# 5_USB-C_Connector.net
KiCad netlist of a schematic drawn in Altium Designer
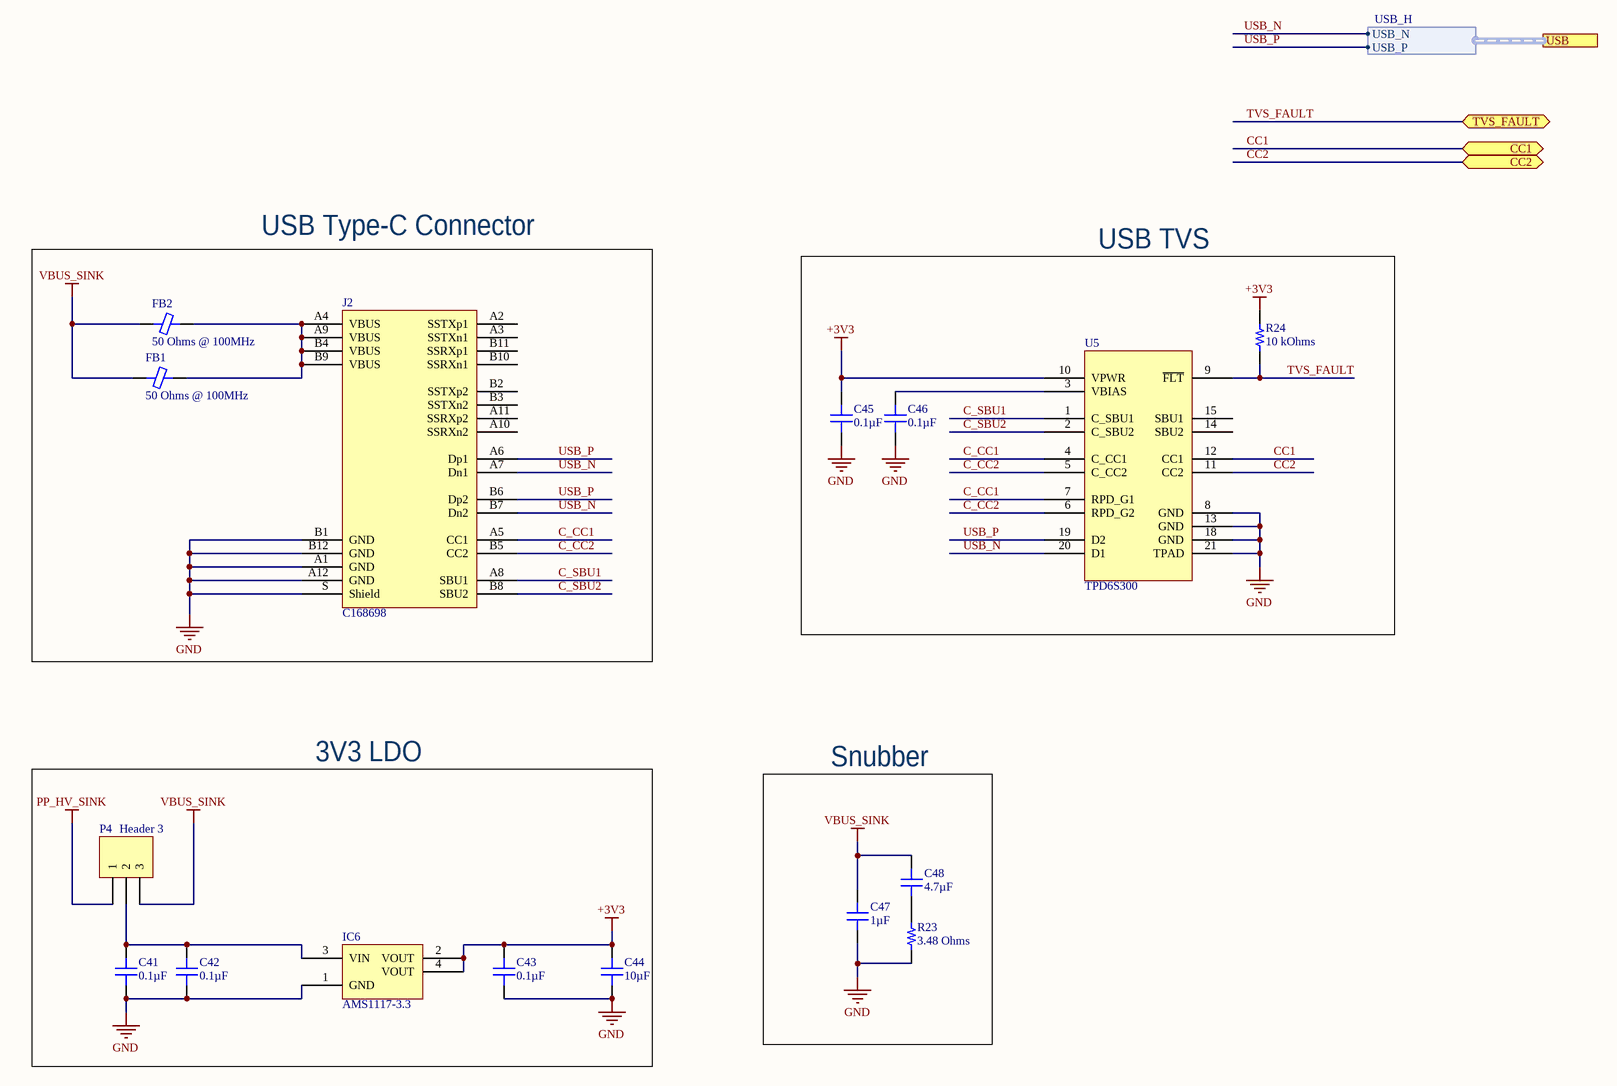
[diagram p0: [5] USB-C Connector.SchDoc]

(export (version "E")
  (design (tool "Eeschema 10.0.6"))
  (components
    (comp (ref "C41")
      (value "0.1µF")
      (footprint "CAP 0805_2012")
      (description "CAP CER 0.1UF 16V X7R 0805")
      (fields
        (field (name "PART NUMBER") "160R15W104KV4T")
        (field (name "MANUFACTURER") "Johanson Dielectrics Inc.")
      )
      (libsource (lib "Celestial Altium Library - altium_library") (part "Capacitor"))
    )
    (comp (ref "C42")
      (value "0.1µF")
      (footprint "CAP 0805_2012")
      (description "CAP CER 0.1UF 16V X7R 0805")
      (fields
        (field (name "PART NUMBER") "160R15W104KV4T")
        (field (name "MANUFACTURER") "Johanson Dielectrics Inc.")
      )
      (libsource (lib "Celestial Altium Library - altium_library") (part "Capacitor"))
    )
    (comp (ref "C43")
      (value "0.1µF")
      (footprint "CAP 0805_2012")
      (description "CAP CER 0.1UF 16V X7R 0805")
      (fields
        (field (name "PART NUMBER") "160R15W104KV4T")
        (field (name "MANUFACTURER") "Johanson Dielectrics Inc.")
      )
      (libsource (lib "Celestial Altium Library - altium_library") (part "Capacitor"))
    )
    (comp (ref "C44")
      (value "10µF")
      (footprint "CAP 1210_3225 - 2.8MM")
      (description "CAP CER 10UF 25V X7R 1210")
      (fields (field (name "PART NUMBER") "C1210C106K3RACAUTO") (field (name "MANUFACTURER") "KEMET"))
      (libsource (lib "Celestial Altium Library - altium_library") (part "Capacitor"))
    )
    (comp (ref "C45")
      (value "0.1µF")
      (footprint "CAP 0603_1608")
      (description "CAP CER 0.1UF 16V X7R 0603")
      (fields
        (field (name "PART NUMBER") "0603B104J160CT")
        (field (name "MANUFACTURER") "Walsin Technology Corporation")
      )
      (libsource (lib "Celestial Altium Library - altium_library") (part "Capacitor"))
    )
    (comp (ref "C46")
      (value "0.1µF")
      (footprint "CAP 0603_1608")
      (description "CAP CER 0.1UF 16V X7R 0603")
      (fields
        (field (name "PART NUMBER") "0603B104J160CT")
        (field (name "MANUFACTURER") "Walsin Technology Corporation")
      )
      (libsource (lib "Celestial Altium Library - altium_library") (part "Capacitor"))
    )
    (comp (ref "C47")
      (value "1µF")
      (footprint "CAP 0805_2012")
      (description "CAP CER 1UF 50V X7R 0805")
      (fields (field (name "PART NUMBER") "08055C105K4Z2A") (field (name "MANUFACTURER") "AVX Corporation"))
      (libsource (lib "Celestial Altium Library - altium_library") (part "Capacitor"))
    )
    (comp (ref "C48")
      (value "4.7µF")
      (footprint "CAP 0805_2012")
      (description "CAP CER 4.7UF 50V JB 0805")
      (fields
        (field (name "PART NUMBER") "C2012JB1H475K125AB")
        (field (name "MANUFACTURER") "TDK Corporation")
      )
      (libsource (lib "Celestial Altium Library - altium_library") (part "Capacitor"))
    )
    (comp (ref "FB1")
      (value "50 Ohms @ 100MHz")
      (footprint "FER 1206_3216")
      (description "FERRITE BEAD 50 OHM 1206 1LN")
      (fields
        (field (name "PART NUMBER") "BLM31SN500SZ1L")
        (field (name "MANUFACTURER") "Murata Electronics")
      )
      (libsource (lib "Celestial Altium Library - altium_library") (part "Ferrite Chip"))
    )
    (comp (ref "FB2")
      (value "50 Ohms @ 100MHz")
      (footprint "FER 1206_3216")
      (description "FERRITE BEAD 50 OHM 1206 1LN")
      (fields
        (field (name "PART NUMBER") "BLM31SN500SZ1L")
        (field (name "MANUFACTURER") "Murata Electronics")
      )
      (libsource (lib "Celestial Altium Library - altium_library") (part "Ferrite Chip"))
    )
    (comp (ref "IC6")
      (value "AMS1117-3.3")
      (footprint "ON SEMI SOT-223 ST(318H)")
      (description "IC REG LDO 3.3V 1A SOT223")
      (fields (field (name "PART NUMBER") "NCP1117ST33T3G") (field (name "MANUFACTURER") "ON Semiconductor"))
      (libsource (lib "Celestial Library Database") (part "ON Semi NCP1117"))
    )
    (comp (ref "J2")
      (value "C168698")
      (footprint "USB4055")
      (description "USB 3.1 TYPE C MID MOUNT HYBRID")
      (fields (field (name "MANUFACTURER") "Jing Extension"))
      (libsource (lib "Celestial Library Database") (part "USB 3.0 Type C"))
    )
    (comp (ref "P4")
      (value "Header 3")
      (footprint "3D FootPrint_Backup:HEADER 2.54MM - duplicate1")
      (description "Header, 3-Pin")
      (fields (field (name "PUBLISHER") "Altium Limited"))
      (libsource (lib "Miscellaneous Connectors") (part "Header 3"))
    )
    (comp (ref "R23")
      (value "3.48 Ohms")
      (footprint "RES 0805_2012")
      (description "RES SMD 3.48 OHM 1% 1/8W 0805")
      (fields (field (name "PART NUMBER") "RC0805FR-073R48L") (field (name "MANUFACTURER") "Yageo"))
      (libsource (lib "Celestial Altium Library - altium_library") (part "Resistor"))
    )
    (comp (ref "R24")
      (value "10 kOhms")
      (footprint "RES 0603_1608")
      (description "RES SMD 10K OHM 5% 1/10W 0603")
      (fields (field (name "PART NUMBER") "CRCW060310K0JNEA") (field (name "MANUFACTURER") "Vishay Dale"))
      (libsource (lib "Celestial Altium Library - altium_library") (part "Resistor"))
    )
    (comp (ref "U5")
      (value "TPD6S300")
      (footprint "Component 3D Footprint:WQFN - 20")
      (libsource (lib "Altium Component") (part "TPD6S300"))
    )
  )
  (nets
    (net (code "2") (name "+3V3") (class "Default")
      (node (ref "C43") (pin "2") (pinfunction "2_2") (pintype "passive"))
      (node (ref "C44") (pin "2") (pinfunction "2_2") (pintype "passive"))
      (node (ref "C45") (pin "2") (pinfunction "2_2") (pintype "passive"))
      (node (ref "IC6") (pin "2") (pinfunction "VOUT_2") (pintype "passive"))
      (node (ref "IC6") (pin "4") (pinfunction "VOUT_4") (pintype "passive"))
      (node (ref "R24") (pin "1") (pinfunction "1_1") (pintype "passive"))
      (node (ref "U5") (pin "10") (pinfunction "VPWR_10") (pintype "passive"))
    )
    (net (code "3") (name "/CC1") (class "Default")
      (node (ref "U5") (pin "12") (pinfunction "CC1_12") (pintype "passive"))
    )
    (net (code "4") (name "/CC2") (class "Default")
      (node (ref "U5") (pin "11") (pinfunction "CC2_11") (pintype "passive"))
    )
    (net (code "5") (name "/C_CC1") (class "Default")
      (node (ref "J2") (pin "A5") (pinfunction "CC1_A5") (pintype "passive"))
      (node (ref "U5") (pin "4") (pinfunction "C_CC1_4") (pintype "passive"))
      (node (ref "U5") (pin "7") (pinfunction "RPD_G1_7") (pintype "passive"))
    )
    (net (code "6") (name "/C_CC2") (class "Default")
      (node (ref "J2") (pin "B5") (pinfunction "CC2_B5") (pintype "passive"))
      (node (ref "U5") (pin "5") (pinfunction "C_CC2_5") (pintype "passive"))
      (node (ref "U5") (pin "6") (pinfunction "RPD_G2_6") (pintype "passive"))
    )
    (net (code "7") (name "/C_SBU1") (class "Default")
      (node (ref "J2") (pin "A8") (pinfunction "SBU1_A8") (pintype "passive"))
      (node (ref "U5") (pin "1") (pinfunction "C_SBU1_1") (pintype "passive"))
    )
    (net (code "8") (name "/C_SBU2") (class "Default")
      (node (ref "J2") (pin "B8") (pinfunction "SBU2_B8") (pintype "passive"))
      (node (ref "U5") (pin "2") (pinfunction "C_SBU2_2") (pintype "passive"))
    )
    (net (code "9") (name "/TVS_FAULT") (class "Default")
      (node (ref "R24") (pin "2") (pinfunction "2_2") (pintype "passive"))
      (node (ref "U5") (pin "9") (pinfunction "~{FLT}_9") (pintype "passive"))
    )
    (net (code "10") (name "/USB_N") (class "Default")
      (node (ref "J2") (pin "A7") (pinfunction "Dn1_A7") (pintype "passive"))
      (node (ref "J2") (pin "B7") (pinfunction "Dn2_B7") (pintype "passive"))
      (node (ref "U5") (pin "20") (pinfunction "D1_20") (pintype "passive"))
    )
    (net (code "11") (name "/USB_P") (class "Default")
      (node (ref "J2") (pin "A6") (pinfunction "Dp1_A6") (pintype "passive"))
      (node (ref "J2") (pin "B6") (pinfunction "Dp2_B6") (pintype "passive"))
      (node (ref "U5") (pin "19") (pinfunction "D2_19") (pintype "passive"))
    )
    (net (code "13") (name "GND") (class "Default")
      (node (ref "C41") (pin "1") (pinfunction "1_1") (pintype "passive"))
      (node (ref "C42") (pin "1") (pinfunction "1_1") (pintype "passive"))
      (node (ref "C43") (pin "1") (pinfunction "1_1") (pintype "passive"))
      (node (ref "C44") (pin "1") (pinfunction "1_1") (pintype "passive"))
      (node (ref "C45") (pin "1") (pinfunction "1_1") (pintype "passive"))
      (node (ref "C46") (pin "1") (pinfunction "1_1") (pintype "passive"))
      (node (ref "C47") (pin "1") (pinfunction "1_1") (pintype "passive"))
      (node (ref "IC6") (pin "1") (pinfunction "GND_1") (pintype "passive"))
      (node (ref "J2") (pin "A1") (pinfunction "GND_A1") (pintype "passive"))
      (node (ref "J2") (pin "A12") (pinfunction "GND_A12") (pintype "passive"))
      (node (ref "J2") (pin "B1") (pinfunction "GND_B1") (pintype "passive"))
      (node (ref "J2") (pin "B12") (pinfunction "GND_B12") (pintype "passive"))
      (node (ref "J2") (pin "S") (pinfunction "Shield_S") (pintype "passive"))
      (node (ref "R23") (pin "1") (pinfunction "1_1") (pintype "passive"))
      (node (ref "U5") (pin "13") (pinfunction "GND_13") (pintype "passive"))
      (node (ref "U5") (pin "18") (pinfunction "GND_18") (pintype "passive"))
      (node (ref "U5") (pin "21") (pinfunction "TPAD_21") (pintype "passive"))
      (node (ref "U5") (pin "8") (pinfunction "GND_8") (pintype "passive"))
    )
    (net (code "14") (name "Net-(C48-Pad2)") (class "Default")
      (node (ref "C48") (pin "2") (pinfunction "2_2") (pintype "passive"))
      (node (ref "R23") (pin "2") (pinfunction "2_2") (pintype "passive"))
    )
    (net (code "15") (name "Net-(FB1-Pad2)") (class "Default")
      (node (ref "FB1") (pin "2") (pinfunction "2_2") (pintype "passive"))
      (node (ref "FB2") (pin "2") (pinfunction "2_2") (pintype "passive"))
      (node (ref "J2") (pin "A4") (pinfunction "VBUS_A4") (pintype "passive"))
      (node (ref "J2") (pin "A9") (pinfunction "VBUS_A9") (pintype "passive"))
      (node (ref "J2") (pin "B4") (pinfunction "VBUS_B4") (pintype "passive"))
      (node (ref "J2") (pin "B9") (pinfunction "VBUS_B9") (pintype "passive"))
    )
    (net (code "16") (name "Net-(IC6-VIN)") (class "Default")
      (node (ref "C41") (pin "2") (pinfunction "2_2") (pintype "passive"))
      (node (ref "C42") (pin "2") (pinfunction "2_2") (pintype "passive"))
      (node (ref "IC6") (pin "3") (pinfunction "VIN_3") (pintype "passive"))
      (node (ref "P4") (pin "2") (pinfunction "2_2") (pintype "passive"))
    )
    (net (code "17") (name "Net-(U5-VBIAS)") (class "Default")
      (node (ref "C46") (pin "2") (pinfunction "2_2") (pintype "passive"))
      (node (ref "U5") (pin "3") (pinfunction "VBIAS_3") (pintype "passive"))
    )
    (net (code "18") (name "PP_HV_SINK") (class "Default")
      (node (ref "P4") (pin "1") (pinfunction "1_1") (pintype "passive"))
    )
    (net (code "19") (name "VBUS_SINK") (class "Default")
      (node (ref "C47") (pin "2") (pinfunction "2_2") (pintype "passive"))
      (node (ref "C48") (pin "1") (pinfunction "1_1") (pintype "passive"))
      (node (ref "FB1") (pin "1") (pinfunction "1_1") (pintype "passive"))
      (node (ref "FB2") (pin "1") (pinfunction "1_1") (pintype "passive"))
      (node (ref "P4") (pin "3") (pinfunction "3_3") (pintype "passive"))
    )
    (net (code "20") (name "unconnected-(J2-SSRXn1-PadB10)") (class "Default")
      (node (ref "J2") (pin "B10") (pinfunction "SSRXn1_B10") (pintype "passive"))
    )
    (net (code "21") (name "unconnected-(J2-SSRXn2-PadA10)") (class "Default")
      (node (ref "J2") (pin "A10") (pinfunction "SSRXn2_A10") (pintype "passive"))
    )
    (net (code "22") (name "unconnected-(J2-SSRXp1-PadB11)") (class "Default")
      (node (ref "J2") (pin "B11") (pinfunction "SSRXp1_B11") (pintype "passive"))
    )
    (net (code "23") (name "unconnected-(J2-SSRXp2-PadA11)") (class "Default")
      (node (ref "J2") (pin "A11") (pinfunction "SSRXp2_A11") (pintype "passive"))
    )
    (net (code "24") (name "unconnected-(J2-SSTXn1-PadA3)") (class "Default")
      (node (ref "J2") (pin "A3") (pinfunction "SSTXn1_A3") (pintype "passive"))
    )
    (net (code "25") (name "unconnected-(J2-SSTXn2-PadB3)") (class "Default")
      (node (ref "J2") (pin "B3") (pinfunction "SSTXn2_B3") (pintype "passive"))
    )
    (net (code "26") (name "unconnected-(J2-SSTXp1-PadA2)") (class "Default")
      (node (ref "J2") (pin "A2") (pinfunction "SSTXp1_A2") (pintype "passive"))
    )
    (net (code "27") (name "unconnected-(J2-SSTXp2-PadB2)") (class "Default")
      (node (ref "J2") (pin "B2") (pinfunction "SSTXp2_B2") (pintype "passive"))
    )
    (net (code "28") (name "unconnected-(U5-NC-Pad16)") (class "Default")
      (node (ref "U5") (pin "16") (pinfunction "NC_16") (pintype "passive"))
    )
    (net (code "29") (name "unconnected-(U5-NC-Pad17)") (class "Default")
      (node (ref "U5") (pin "17") (pinfunction "NC_17") (pintype "passive"))
    )
    (net (code "30") (name "unconnected-(U5-SBU1-Pad15)") (class "Default")
      (node (ref "U5") (pin "15") (pinfunction "SBU1_15") (pintype "passive"))
    )
    (net (code "31") (name "unconnected-(U5-SBU2-Pad14)") (class "Default")
      (node (ref "U5") (pin "14") (pinfunction "SBU2_14") (pintype "passive"))
    )
  )
)
